# Register.net
KiCad netlist of a schematic drawn in EAGLE
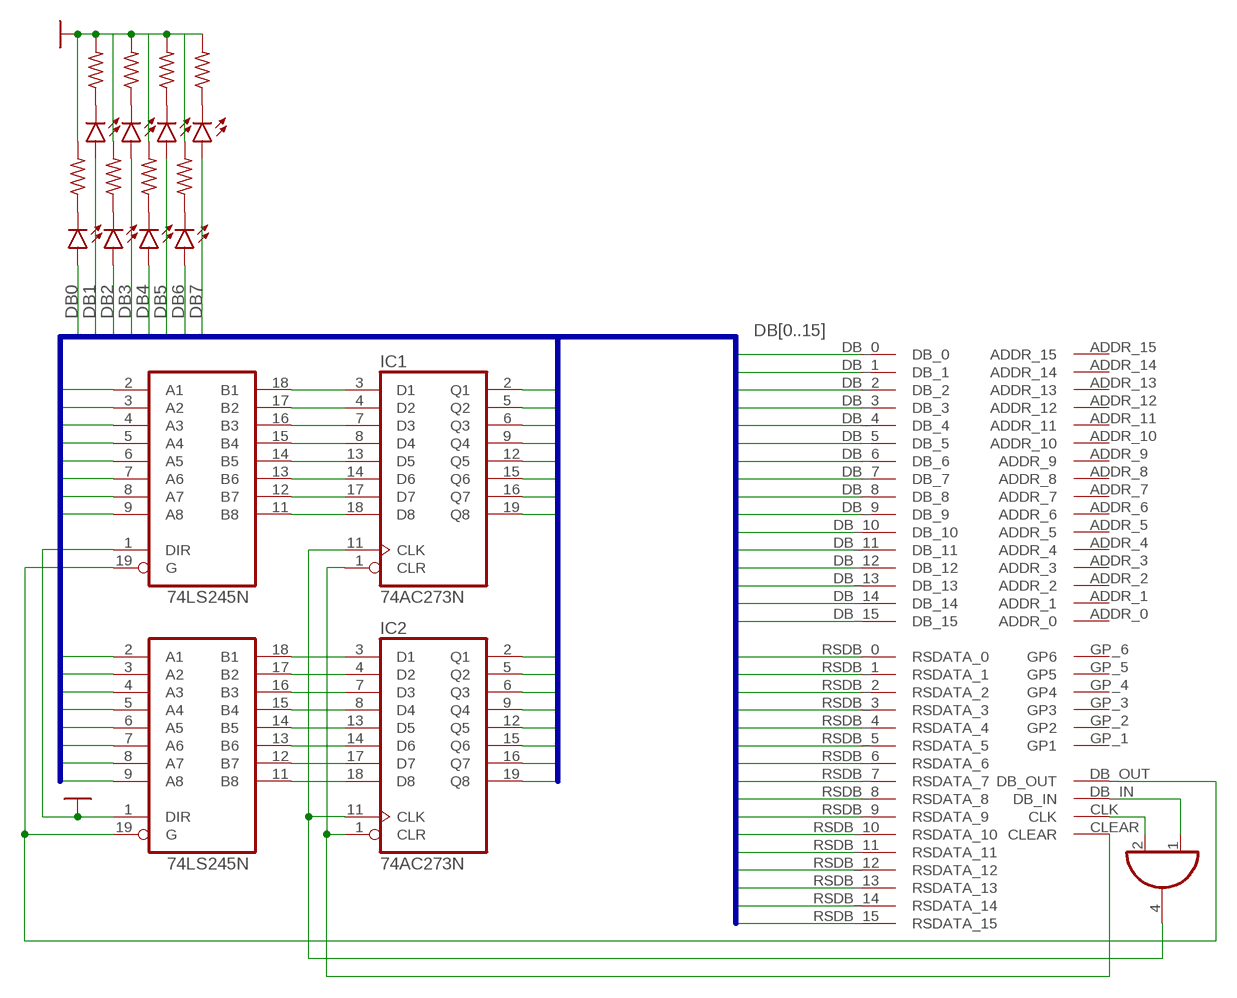
[diagram p0: schematic, sheet 1]

(export (version "E")
  (design (tool "Eeschema 10.0.6"))
  (components
    (comp (ref "IC1")
      (value "74AC273N")
      (footprint "eagle-import:DIL20")
      (libsource (lib "eagle-import") (part "74273NAC"))
    )
    (comp (ref "IC2")
      (value "74AC273N")
      (footprint "eagle-import:DIL20")
      (libsource (lib "eagle-import") (part "74273NAC"))
    )
    (comp (ref "IC4")
      (value "74AHC1G08DCK")
      (footprint "eagle-import:SC70-5")
      (libsource (lib "eagle-import") (part "741G08DCKAHC"))
    )
    (comp (ref "LED_A_REG_1")
      (value "LED")
      (footprint "eagle-import:LED5MM")
      (libsource (lib "eagle-import") (part "LED5MM"))
    )
    (comp (ref "LED_A_REG_2")
      (value "LED")
      (footprint "eagle-import:LED5MM")
      (libsource (lib "eagle-import") (part "LED5MM"))
    )
    (comp (ref "LED_A_REG_3")
      (value "LED")
      (footprint "eagle-import:LED5MM")
      (libsource (lib "eagle-import") (part "LED5MM"))
    )
    (comp (ref "LED_A_REG_4")
      (value "LED")
      (footprint "eagle-import:LED5MM")
      (libsource (lib "eagle-import") (part "LED5MM"))
    )
    (comp (ref "LED_A_REG_5")
      (value "LED")
      (footprint "eagle-import:LED5MM")
      (libsource (lib "eagle-import") (part "LED5MM"))
    )
    (comp (ref "LED_A_REG_6")
      (value "LED")
      (footprint "eagle-import:LED5MM")
      (libsource (lib "eagle-import") (part "LED5MM"))
    )
    (comp (ref "LED_A_REG_7")
      (value "LED")
      (footprint "eagle-import:LED5MM")
      (libsource (lib "eagle-import") (part "LED5MM"))
    )
    (comp (ref "LED_A_REG_8")
      (value "LED")
      (footprint "eagle-import:LED5MM")
      (libsource (lib "eagle-import") (part "LED5MM"))
    )
    (comp (ref "OUTPUT_BUFFER_REG_A")
      (value "74LS245N")
      (footprint "eagle-import:DIL20")
      (libsource (lib "eagle-import") (part "74245NLS"))
    )
    (comp (ref "OUTPUT_BUFFER_REG_A1")
      (value "74LS245N")
      (footprint "eagle-import:DIL20")
      (libsource (lib "eagle-import") (part "74245NLS"))
    )
    (comp (ref "R1")
      (value "~220")
      (footprint "eagle-import:0204_7")
      (libsource (lib "eagle-import") (part "R-US_0204/7"))
    )
    (comp (ref "R2")
      (value "~220")
      (footprint "eagle-import:0204_7")
      (libsource (lib "eagle-import") (part "R-US_0204/7"))
    )
    (comp (ref "R3")
      (value "~220")
      (footprint "eagle-import:0204_7")
      (libsource (lib "eagle-import") (part "R-US_0204/7"))
    )
    (comp (ref "R4")
      (value "~220")
      (footprint "eagle-import:0204_7")
      (libsource (lib "eagle-import") (part "R-US_0204/7"))
    )
    (comp (ref "R5")
      (value "~220")
      (footprint "eagle-import:0204_7")
      (libsource (lib "eagle-import") (part "R-US_0204/7"))
    )
    (comp (ref "R6")
      (value "~220")
      (footprint "eagle-import:0204_7")
      (libsource (lib "eagle-import") (part "R-US_0204/7"))
    )
    (comp (ref "R7")
      (value "~220")
      (footprint "eagle-import:0204_7")
      (libsource (lib "eagle-import") (part "R-US_0204/7"))
    )
    (comp (ref "R8")
      (value "~220")
      (footprint "eagle-import:0204_7")
      (libsource (lib "eagle-import") (part "R-US_0204/7"))
    )
    (comp (ref "U$1")
      (value "BACKPLATE_INTERFACE")
      (footprint "eagle-import:BACK_INTERFACE-FOOT")
      (libsource (lib "eagle-import") (part "BACKPLATE_INTERFACE"))
    )
  )
  (nets
    (net (code "1") (name "/DB0") (class "Default")
      (node (ref "IC1") (pin "2") (pinfunction "Q1_2") (pintype "output"))
      (node (ref "LED_A_REG_1") (pin "A") (pinfunction "A_A") (pintype "passive"))
      (node (ref "OUTPUT_BUFFER_REG_A1") (pin "2") (pinfunction "A1_2") (pintype "bidirectional"))
      (node (ref "U$1") (pin "DB_0") (pinfunction "DB_0_DB_0") (pintype "bidirectional"))
      (node (ref "U$1") (pin "RSDB_0") (pinfunction "RSDATA_0_RSDB_0") (pintype "bidirectional"))
    )
    (net (code "2") (name "/DB1") (class "Default")
      (node (ref "IC1") (pin "5") (pinfunction "Q2_5") (pintype "output"))
      (node (ref "LED_A_REG_2") (pin "A") (pinfunction "A_A") (pintype "passive"))
      (node (ref "OUTPUT_BUFFER_REG_A1") (pin "3") (pinfunction "A2_3") (pintype "bidirectional"))
      (node (ref "U$1") (pin "DB_1") (pinfunction "DB_1_DB_1") (pintype "bidirectional"))
      (node (ref "U$1") (pin "RSDB_1") (pinfunction "RSDATA_1_RSDB_1") (pintype "bidirectional"))
    )
    (net (code "3") (name "/DB2") (class "Default")
      (node (ref "IC1") (pin "6") (pinfunction "Q3_6") (pintype "output"))
      (node (ref "LED_A_REG_3") (pin "A") (pinfunction "A_A") (pintype "passive"))
      (node (ref "OUTPUT_BUFFER_REG_A1") (pin "4") (pinfunction "A3_4") (pintype "bidirectional"))
      (node (ref "U$1") (pin "DB_2") (pinfunction "DB_2_DB_2") (pintype "bidirectional"))
      (node (ref "U$1") (pin "RSDB_2") (pinfunction "RSDATA_2_RSDB_2") (pintype "bidirectional"))
    )
    (net (code "4") (name "/DB3") (class "Default")
      (node (ref "IC1") (pin "9") (pinfunction "Q4_9") (pintype "output"))
      (node (ref "LED_A_REG_4") (pin "A") (pinfunction "A_A") (pintype "passive"))
      (node (ref "OUTPUT_BUFFER_REG_A1") (pin "5") (pinfunction "A4_5") (pintype "bidirectional"))
      (node (ref "U$1") (pin "DB_3") (pinfunction "DB_3_DB_3") (pintype "bidirectional"))
      (node (ref "U$1") (pin "RSDB_3") (pinfunction "RSDATA_3_RSDB_3") (pintype "bidirectional"))
    )
    (net (code "5") (name "/DB4") (class "Default")
      (node (ref "IC1") (pin "12") (pinfunction "Q5_12") (pintype "output"))
      (node (ref "LED_A_REG_5") (pin "A") (pinfunction "A_A") (pintype "passive"))
      (node (ref "OUTPUT_BUFFER_REG_A1") (pin "6") (pinfunction "A5_6") (pintype "bidirectional"))
      (node (ref "U$1") (pin "DB_4") (pinfunction "DB_4_DB_4") (pintype "bidirectional"))
      (node (ref "U$1") (pin "RSDB_4") (pinfunction "RSDATA_4_RSDB_4") (pintype "bidirectional"))
    )
    (net (code "6") (name "/DB5") (class "Default")
      (node (ref "IC1") (pin "15") (pinfunction "Q6_15") (pintype "output"))
      (node (ref "LED_A_REG_6") (pin "A") (pinfunction "A_A") (pintype "passive"))
      (node (ref "OUTPUT_BUFFER_REG_A1") (pin "7") (pinfunction "A6_7") (pintype "bidirectional"))
      (node (ref "U$1") (pin "DB_5") (pinfunction "DB_5_DB_5") (pintype "bidirectional"))
      (node (ref "U$1") (pin "RSDB_5") (pinfunction "RSDATA_5_RSDB_5") (pintype "bidirectional"))
    )
    (net (code "7") (name "/DB6") (class "Default")
      (node (ref "IC1") (pin "16") (pinfunction "Q7_16") (pintype "output"))
      (node (ref "LED_A_REG_7") (pin "A") (pinfunction "A_A") (pintype "passive"))
      (node (ref "OUTPUT_BUFFER_REG_A1") (pin "8") (pinfunction "A7_8") (pintype "bidirectional"))
      (node (ref "U$1") (pin "DB_6") (pinfunction "DB_6_DB_6") (pintype "bidirectional"))
      (node (ref "U$1") (pin "RSDB_6") (pinfunction "RSDATA_6_RSDB_6") (pintype "bidirectional"))
    )
    (net (code "8") (name "/DB7") (class "Default")
      (node (ref "IC1") (pin "19") (pinfunction "Q8_19") (pintype "output"))
      (node (ref "LED_A_REG_8") (pin "A") (pinfunction "A_A") (pintype "passive"))
      (node (ref "OUTPUT_BUFFER_REG_A1") (pin "9") (pinfunction "A8_9") (pintype "bidirectional"))
      (node (ref "U$1") (pin "DB_7") (pinfunction "DB_7_DB_7") (pintype "bidirectional"))
      (node (ref "U$1") (pin "RSDB_7") (pinfunction "RSDATA_7_RSDB_7") (pintype "bidirectional"))
    )
    (net (code "9") (name "/DB8") (class "Default")
      (node (ref "IC2") (pin "2") (pinfunction "Q1_2") (pintype "output"))
      (node (ref "OUTPUT_BUFFER_REG_A") (pin "2") (pinfunction "A1_2") (pintype "bidirectional"))
      (node (ref "U$1") (pin "DB_8") (pinfunction "DB_8_DB_8") (pintype "bidirectional"))
      (node (ref "U$1") (pin "RSDB_8") (pinfunction "RSDATA_8_RSDB_8") (pintype "bidirectional"))
    )
    (net (code "10") (name "/DB9") (class "Default")
      (node (ref "IC2") (pin "5") (pinfunction "Q2_5") (pintype "output"))
      (node (ref "OUTPUT_BUFFER_REG_A") (pin "3") (pinfunction "A2_3") (pintype "bidirectional"))
      (node (ref "U$1") (pin "DB_9") (pinfunction "DB_9_DB_9") (pintype "bidirectional"))
      (node (ref "U$1") (pin "RSDB_9") (pinfunction "RSDATA_9_RSDB_9") (pintype "bidirectional"))
    )
    (net (code "11") (name "/DB10") (class "Default")
      (node (ref "IC2") (pin "6") (pinfunction "Q3_6") (pintype "output"))
      (node (ref "OUTPUT_BUFFER_REG_A") (pin "4") (pinfunction "A3_4") (pintype "bidirectional"))
      (node (ref "U$1") (pin "DB_10") (pinfunction "DB_10_DB_10") (pintype "bidirectional"))
      (node (ref "U$1") (pin "RSDB_10") (pinfunction "RSDATA_10_RSDB_10") (pintype "bidirectional"))
    )
    (net (code "12") (name "/DB11") (class "Default")
      (node (ref "IC2") (pin "9") (pinfunction "Q4_9") (pintype "output"))
      (node (ref "OUTPUT_BUFFER_REG_A") (pin "5") (pinfunction "A4_5") (pintype "bidirectional"))
      (node (ref "U$1") (pin "DB_11") (pinfunction "DB_11_DB_11") (pintype "bidirectional"))
      (node (ref "U$1") (pin "RSDB_11") (pinfunction "RSDATA_11_RSDB_11") (pintype "bidirectional"))
    )
    (net (code "13") (name "/DB12") (class "Default")
      (node (ref "IC2") (pin "12") (pinfunction "Q5_12") (pintype "output"))
      (node (ref "OUTPUT_BUFFER_REG_A") (pin "6") (pinfunction "A5_6") (pintype "bidirectional"))
      (node (ref "U$1") (pin "DB_12") (pinfunction "DB_12_DB_12") (pintype "bidirectional"))
      (node (ref "U$1") (pin "RSDB_12") (pinfunction "RSDATA_12_RSDB_12") (pintype "bidirectional"))
    )
    (net (code "14") (name "/DB13") (class "Default")
      (node (ref "IC2") (pin "15") (pinfunction "Q6_15") (pintype "output"))
      (node (ref "OUTPUT_BUFFER_REG_A") (pin "7") (pinfunction "A6_7") (pintype "bidirectional"))
      (node (ref "U$1") (pin "DB_13") (pinfunction "DB_13_DB_13") (pintype "bidirectional"))
      (node (ref "U$1") (pin "RSDB_13") (pinfunction "RSDATA_13_RSDB_13") (pintype "bidirectional"))
    )
    (net (code "15") (name "/DB14") (class "Default")
      (node (ref "IC2") (pin "16") (pinfunction "Q7_16") (pintype "output"))
      (node (ref "OUTPUT_BUFFER_REG_A") (pin "8") (pinfunction "A7_8") (pintype "bidirectional"))
      (node (ref "U$1") (pin "DB_14") (pinfunction "DB_14_DB_14") (pintype "bidirectional"))
      (node (ref "U$1") (pin "RSDB_14") (pinfunction "RSDATA_14_RSDB_14") (pintype "bidirectional"))
    )
    (net (code "16") (name "/DB15") (class "Default")
      (node (ref "IC2") (pin "19") (pinfunction "Q8_19") (pintype "output"))
      (node (ref "OUTPUT_BUFFER_REG_A") (pin "9") (pinfunction "A8_9") (pintype "bidirectional"))
      (node (ref "U$1") (pin "DB_15") (pinfunction "DB_15_DB_15") (pintype "bidirectional"))
      (node (ref "U$1") (pin "RSDB_15") (pinfunction "RSDATA_15_RSDB_15") (pintype "bidirectional"))
    )
    (net (code "18") (name "GND") (class "Default")
      (node (ref "OUTPUT_BUFFER_REG_A") (pin "1") (pinfunction "DIR_1") (pintype "input"))
      (node (ref "OUTPUT_BUFFER_REG_A1") (pin "1") (pinfunction "DIR_1") (pintype "input"))
      (node (ref "R1") (pin "2") (pinfunction "2_2") (pintype "passive"))
      (node (ref "R2") (pin "2") (pinfunction "2_2") (pintype "passive"))
      (node (ref "R4") (pin "2") (pinfunction "2_2") (pintype "passive"))
      (node (ref "R6") (pin "2") (pinfunction "2_2") (pintype "passive"))
      (node (ref "R8") (pin "2") (pinfunction "2_2") (pintype "passive"))
    )
    (net (code "19") (name "Net-(IC1A-CLK)") (class "Default")
      (node (ref "IC1") (pin "11") (pinfunction "CLK_11") (pintype "input"))
      (node (ref "IC2") (pin "11") (pinfunction "CLK_11") (pintype "input"))
      (node (ref "IC4") (pin "4") (pinfunction "O_4") (pintype "output"))
    )
    (net (code "20") (name "Net-(IC1A-CLR)") (class "Default")
      (node (ref "IC1") (pin "1") (pinfunction "CLR_1") (pintype "input"))
      (node (ref "IC2") (pin "1") (pinfunction "CLR_1") (pintype "input"))
      (node (ref "U$1") (pin "CLEAR") (pinfunction "CLEAR_CLEAR") (pintype "bidirectional"))
    )
    (net (code "21") (name "Net-(IC1A-D1)") (class "Default")
      (node (ref "IC1") (pin "3") (pinfunction "D1_3") (pintype "input"))
      (node (ref "OUTPUT_BUFFER_REG_A1") (pin "18") (pinfunction "B1_18") (pintype "bidirectional"))
    )
    (net (code "22") (name "Net-(IC1A-D2)") (class "Default")
      (node (ref "IC1") (pin "4") (pinfunction "D2_4") (pintype "input"))
      (node (ref "OUTPUT_BUFFER_REG_A1") (pin "17") (pinfunction "B2_17") (pintype "bidirectional"))
    )
    (net (code "23") (name "Net-(IC1A-D3)") (class "Default")
      (node (ref "IC1") (pin "7") (pinfunction "D3_7") (pintype "input"))
      (node (ref "OUTPUT_BUFFER_REG_A1") (pin "16") (pinfunction "B3_16") (pintype "bidirectional"))
    )
    (net (code "24") (name "Net-(IC1A-D4)") (class "Default")
      (node (ref "IC1") (pin "8") (pinfunction "D4_8") (pintype "input"))
      (node (ref "OUTPUT_BUFFER_REG_A1") (pin "15") (pinfunction "B4_15") (pintype "bidirectional"))
    )
    (net (code "25") (name "Net-(IC1A-D5)") (class "Default")
      (node (ref "IC1") (pin "13") (pinfunction "D5_13") (pintype "input"))
      (node (ref "OUTPUT_BUFFER_REG_A1") (pin "14") (pinfunction "B5_14") (pintype "bidirectional"))
    )
    (net (code "26") (name "Net-(IC1A-D6)") (class "Default")
      (node (ref "IC1") (pin "14") (pinfunction "D6_14") (pintype "input"))
      (node (ref "OUTPUT_BUFFER_REG_A1") (pin "13") (pinfunction "B6_13") (pintype "bidirectional"))
    )
    (net (code "27") (name "Net-(IC1A-D7)") (class "Default")
      (node (ref "IC1") (pin "17") (pinfunction "D7_17") (pintype "input"))
      (node (ref "OUTPUT_BUFFER_REG_A1") (pin "12") (pinfunction "B7_12") (pintype "bidirectional"))
    )
    (net (code "28") (name "Net-(IC1A-D8)") (class "Default")
      (node (ref "IC1") (pin "18") (pinfunction "D8_18") (pintype "input"))
      (node (ref "OUTPUT_BUFFER_REG_A1") (pin "11") (pinfunction "B8_11") (pintype "bidirectional"))
    )
    (net (code "29") (name "Net-(IC2A-D1)") (class "Default")
      (node (ref "IC2") (pin "3") (pinfunction "D1_3") (pintype "input"))
      (node (ref "OUTPUT_BUFFER_REG_A") (pin "18") (pinfunction "B1_18") (pintype "bidirectional"))
    )
    (net (code "30") (name "Net-(IC2A-D2)") (class "Default")
      (node (ref "IC2") (pin "4") (pinfunction "D2_4") (pintype "input"))
      (node (ref "OUTPUT_BUFFER_REG_A") (pin "17") (pinfunction "B2_17") (pintype "bidirectional"))
    )
    (net (code "31") (name "Net-(IC2A-D3)") (class "Default")
      (node (ref "IC2") (pin "7") (pinfunction "D3_7") (pintype "input"))
      (node (ref "OUTPUT_BUFFER_REG_A") (pin "16") (pinfunction "B3_16") (pintype "bidirectional"))
    )
    (net (code "32") (name "Net-(IC2A-D4)") (class "Default")
      (node (ref "IC2") (pin "8") (pinfunction "D4_8") (pintype "input"))
      (node (ref "OUTPUT_BUFFER_REG_A") (pin "15") (pinfunction "B4_15") (pintype "bidirectional"))
    )
    (net (code "33") (name "Net-(IC2A-D5)") (class "Default")
      (node (ref "IC2") (pin "13") (pinfunction "D5_13") (pintype "input"))
      (node (ref "OUTPUT_BUFFER_REG_A") (pin "14") (pinfunction "B5_14") (pintype "bidirectional"))
    )
    (net (code "34") (name "Net-(IC2A-D6)") (class "Default")
      (node (ref "IC2") (pin "14") (pinfunction "D6_14") (pintype "input"))
      (node (ref "OUTPUT_BUFFER_REG_A") (pin "13") (pinfunction "B6_13") (pintype "bidirectional"))
    )
    (net (code "35") (name "Net-(IC2A-D7)") (class "Default")
      (node (ref "IC2") (pin "17") (pinfunction "D7_17") (pintype "input"))
      (node (ref "OUTPUT_BUFFER_REG_A") (pin "12") (pinfunction "B7_12") (pintype "bidirectional"))
    )
    (net (code "36") (name "Net-(IC2A-D8)") (class "Default")
      (node (ref "IC2") (pin "18") (pinfunction "D8_18") (pintype "input"))
      (node (ref "OUTPUT_BUFFER_REG_A") (pin "11") (pinfunction "B8_11") (pintype "bidirectional"))
    )
    (net (code "37") (name "Net-(IC4A-I0)") (class "Default")
      (node (ref "IC4") (pin "1") (pinfunction "I0_1") (pintype "input"))
      (node (ref "U$1") (pin "DB_IN") (pinfunction "DB_IN_DB_IN") (pintype "bidirectional"))
    )
    (net (code "38") (name "Net-(IC4A-I1)") (class "Default")
      (node (ref "IC4") (pin "2") (pinfunction "I1_2") (pintype "input"))
      (node (ref "U$1") (pin "CLK") (pinfunction "CLK_CLK") (pintype "bidirectional"))
    )
    (net (code "39") (name "Net-(LED_A_REG_1-C)") (class "Default")
      (node (ref "LED_A_REG_1") (pin "K") (pinfunction "C_K") (pintype "passive"))
      (node (ref "R1") (pin "1") (pinfunction "1_1") (pintype "passive"))
    )
    (net (code "40") (name "Net-(LED_A_REG_2-C)") (class "Default")
      (node (ref "LED_A_REG_2") (pin "K") (pinfunction "C_K") (pintype "passive"))
      (node (ref "R2") (pin "1") (pinfunction "1_1") (pintype "passive"))
    )
    (net (code "41") (name "Net-(LED_A_REG_3-C)") (class "Default")
      (node (ref "LED_A_REG_3") (pin "K") (pinfunction "C_K") (pintype "passive"))
      (node (ref "R3") (pin "1") (pinfunction "1_1") (pintype "passive"))
    )
    (net (code "42") (name "Net-(LED_A_REG_4-C)") (class "Default")
      (node (ref "LED_A_REG_4") (pin "K") (pinfunction "C_K") (pintype "passive"))
      (node (ref "R4") (pin "1") (pinfunction "1_1") (pintype "passive"))
    )
    (net (code "43") (name "Net-(LED_A_REG_5-C)") (class "Default")
      (node (ref "LED_A_REG_5") (pin "K") (pinfunction "C_K") (pintype "passive"))
      (node (ref "R5") (pin "1") (pinfunction "1_1") (pintype "passive"))
    )
    (net (code "44") (name "Net-(LED_A_REG_6-C)") (class "Default")
      (node (ref "LED_A_REG_6") (pin "K") (pinfunction "C_K") (pintype "passive"))
      (node (ref "R6") (pin "1") (pinfunction "1_1") (pintype "passive"))
    )
    (net (code "45") (name "Net-(LED_A_REG_7-C)") (class "Default")
      (node (ref "LED_A_REG_7") (pin "K") (pinfunction "C_K") (pintype "passive"))
      (node (ref "R7") (pin "1") (pinfunction "1_1") (pintype "passive"))
    )
    (net (code "46") (name "Net-(LED_A_REG_8-C)") (class "Default")
      (node (ref "LED_A_REG_8") (pin "K") (pinfunction "C_K") (pintype "passive"))
      (node (ref "R8") (pin "1") (pinfunction "1_1") (pintype "passive"))
    )
    (net (code "47") (name "Net-(OUTPUT_BUFFER_REG_A1A-G)") (class "Default")
      (node (ref "OUTPUT_BUFFER_REG_A") (pin "19") (pinfunction "G_19") (pintype "input"))
      (node (ref "OUTPUT_BUFFER_REG_A1") (pin "19") (pinfunction "G_19") (pintype "input"))
      (node (ref "U$1") (pin "DB_OUT") (pinfunction "DB_OUT_DB_OUT") (pintype "bidirectional"))
    )
    (net (code "48") (name "unconnected-(R3-Pad2)") (class "Default")
      (node (ref "R3") (pin "2") (pinfunction "2_2") (pintype "passive"))
    )
    (net (code "49") (name "unconnected-(R5-Pad2)") (class "Default")
      (node (ref "R5") (pin "2") (pinfunction "2_2") (pintype "passive"))
    )
    (net (code "50") (name "unconnected-(R7-Pad2)") (class "Default")
      (node (ref "R7") (pin "2") (pinfunction "2_2") (pintype "passive"))
    )
    (net (code "51") (name "unconnected-(U$1-PadADDR_0)") (class "Default")
      (node (ref "U$1") (pin "ADDR_0") (pinfunction "ADDR_0_ADDR_0") (pintype "bidirectional"))
    )
    (net (code "52") (name "unconnected-(U$1-PadADDR_1)") (class "Default")
      (node (ref "U$1") (pin "ADDR_1") (pinfunction "ADDR_1_ADDR_1") (pintype "bidirectional"))
    )
    (net (code "53") (name "unconnected-(U$1-PadADDR_2)") (class "Default")
      (node (ref "U$1") (pin "ADDR_2") (pinfunction "ADDR_2_ADDR_2") (pintype "bidirectional"))
    )
    (net (code "54") (name "unconnected-(U$1-PadADDR_3)") (class "Default")
      (node (ref "U$1") (pin "ADDR_3") (pinfunction "ADDR_3_ADDR_3") (pintype "bidirectional"))
    )
    (net (code "55") (name "unconnected-(U$1-PadADDR_4)") (class "Default")
      (node (ref "U$1") (pin "ADDR_4") (pinfunction "ADDR_4_ADDR_4") (pintype "bidirectional"))
    )
    (net (code "56") (name "unconnected-(U$1-PadADDR_5)") (class "Default")
      (node (ref "U$1") (pin "ADDR_5") (pinfunction "ADDR_5_ADDR_5") (pintype "bidirectional"))
    )
    (net (code "57") (name "unconnected-(U$1-PadADDR_6)") (class "Default")
      (node (ref "U$1") (pin "ADDR_6") (pinfunction "ADDR_6_ADDR_6") (pintype "bidirectional"))
    )
    (net (code "58") (name "unconnected-(U$1-PadADDR_7)") (class "Default")
      (node (ref "U$1") (pin "ADDR_7") (pinfunction "ADDR_7_ADDR_7") (pintype "bidirectional"))
    )
    (net (code "59") (name "unconnected-(U$1-PadADDR_8)") (class "Default")
      (node (ref "U$1") (pin "ADDR_8") (pinfunction "ADDR_8_ADDR_8") (pintype "bidirectional"))
    )
    (net (code "60") (name "unconnected-(U$1-PadADDR_9)") (class "Default")
      (node (ref "U$1") (pin "ADDR_9") (pinfunction "ADDR_9_ADDR_9") (pintype "bidirectional"))
    )
    (net (code "61") (name "unconnected-(U$1-PadADDR_10)") (class "Default")
      (node (ref "U$1") (pin "ADDR_10") (pinfunction "ADDR_10_ADDR_10") (pintype "bidirectional"))
    )
    (net (code "62") (name "unconnected-(U$1-PadADDR_11)") (class "Default")
      (node (ref "U$1") (pin "ADDR_11") (pinfunction "ADDR_11_ADDR_11") (pintype "bidirectional"))
    )
    (net (code "63") (name "unconnected-(U$1-PadADDR_12)") (class "Default")
      (node (ref "U$1") (pin "ADDR_12") (pinfunction "ADDR_12_ADDR_12") (pintype "bidirectional"))
    )
    (net (code "64") (name "unconnected-(U$1-PadADDR_13)") (class "Default")
      (node (ref "U$1") (pin "ADDR_13") (pinfunction "ADDR_13_ADDR_13") (pintype "bidirectional"))
    )
    (net (code "65") (name "unconnected-(U$1-PadADDR_14)") (class "Default")
      (node (ref "U$1") (pin "ADDR_14") (pinfunction "ADDR_14_ADDR_14") (pintype "bidirectional"))
    )
    (net (code "66") (name "unconnected-(U$1-PadADDR_15)") (class "Default")
      (node (ref "U$1") (pin "ADDR_15") (pinfunction "ADDR_15_ADDR_15") (pintype "bidirectional"))
    )
    (net (code "67") (name "unconnected-(U$1A-GP1-PadGP_1)") (class "Default")
      (node (ref "U$1") (pin "GP_1") (pinfunction "GP1_GP_1") (pintype "bidirectional"))
    )
    (net (code "68") (name "unconnected-(U$1A-GP2-PadGP_2)") (class "Default")
      (node (ref "U$1") (pin "GP_2") (pinfunction "GP2_GP_2") (pintype "bidirectional"))
    )
    (net (code "69") (name "unconnected-(U$1A-GP3-PadGP_3)") (class "Default")
      (node (ref "U$1") (pin "GP_3") (pinfunction "GP3_GP_3") (pintype "bidirectional"))
    )
    (net (code "70") (name "unconnected-(U$1A-GP4-PadGP_4)") (class "Default")
      (node (ref "U$1") (pin "GP_4") (pinfunction "GP4_GP_4") (pintype "bidirectional"))
    )
    (net (code "71") (name "unconnected-(U$1A-GP5-PadGP_5)") (class "Default")
      (node (ref "U$1") (pin "GP_5") (pinfunction "GP5_GP_5") (pintype "bidirectional"))
    )
    (net (code "72") (name "unconnected-(U$1A-GP6-PadGP_6)") (class "Default")
      (node (ref "U$1") (pin "GP_6") (pinfunction "GP6_GP_6") (pintype "bidirectional"))
    )
  )
)
